# Sheet1.net
KiCad netlist of a schematic drawn in Altium Designer
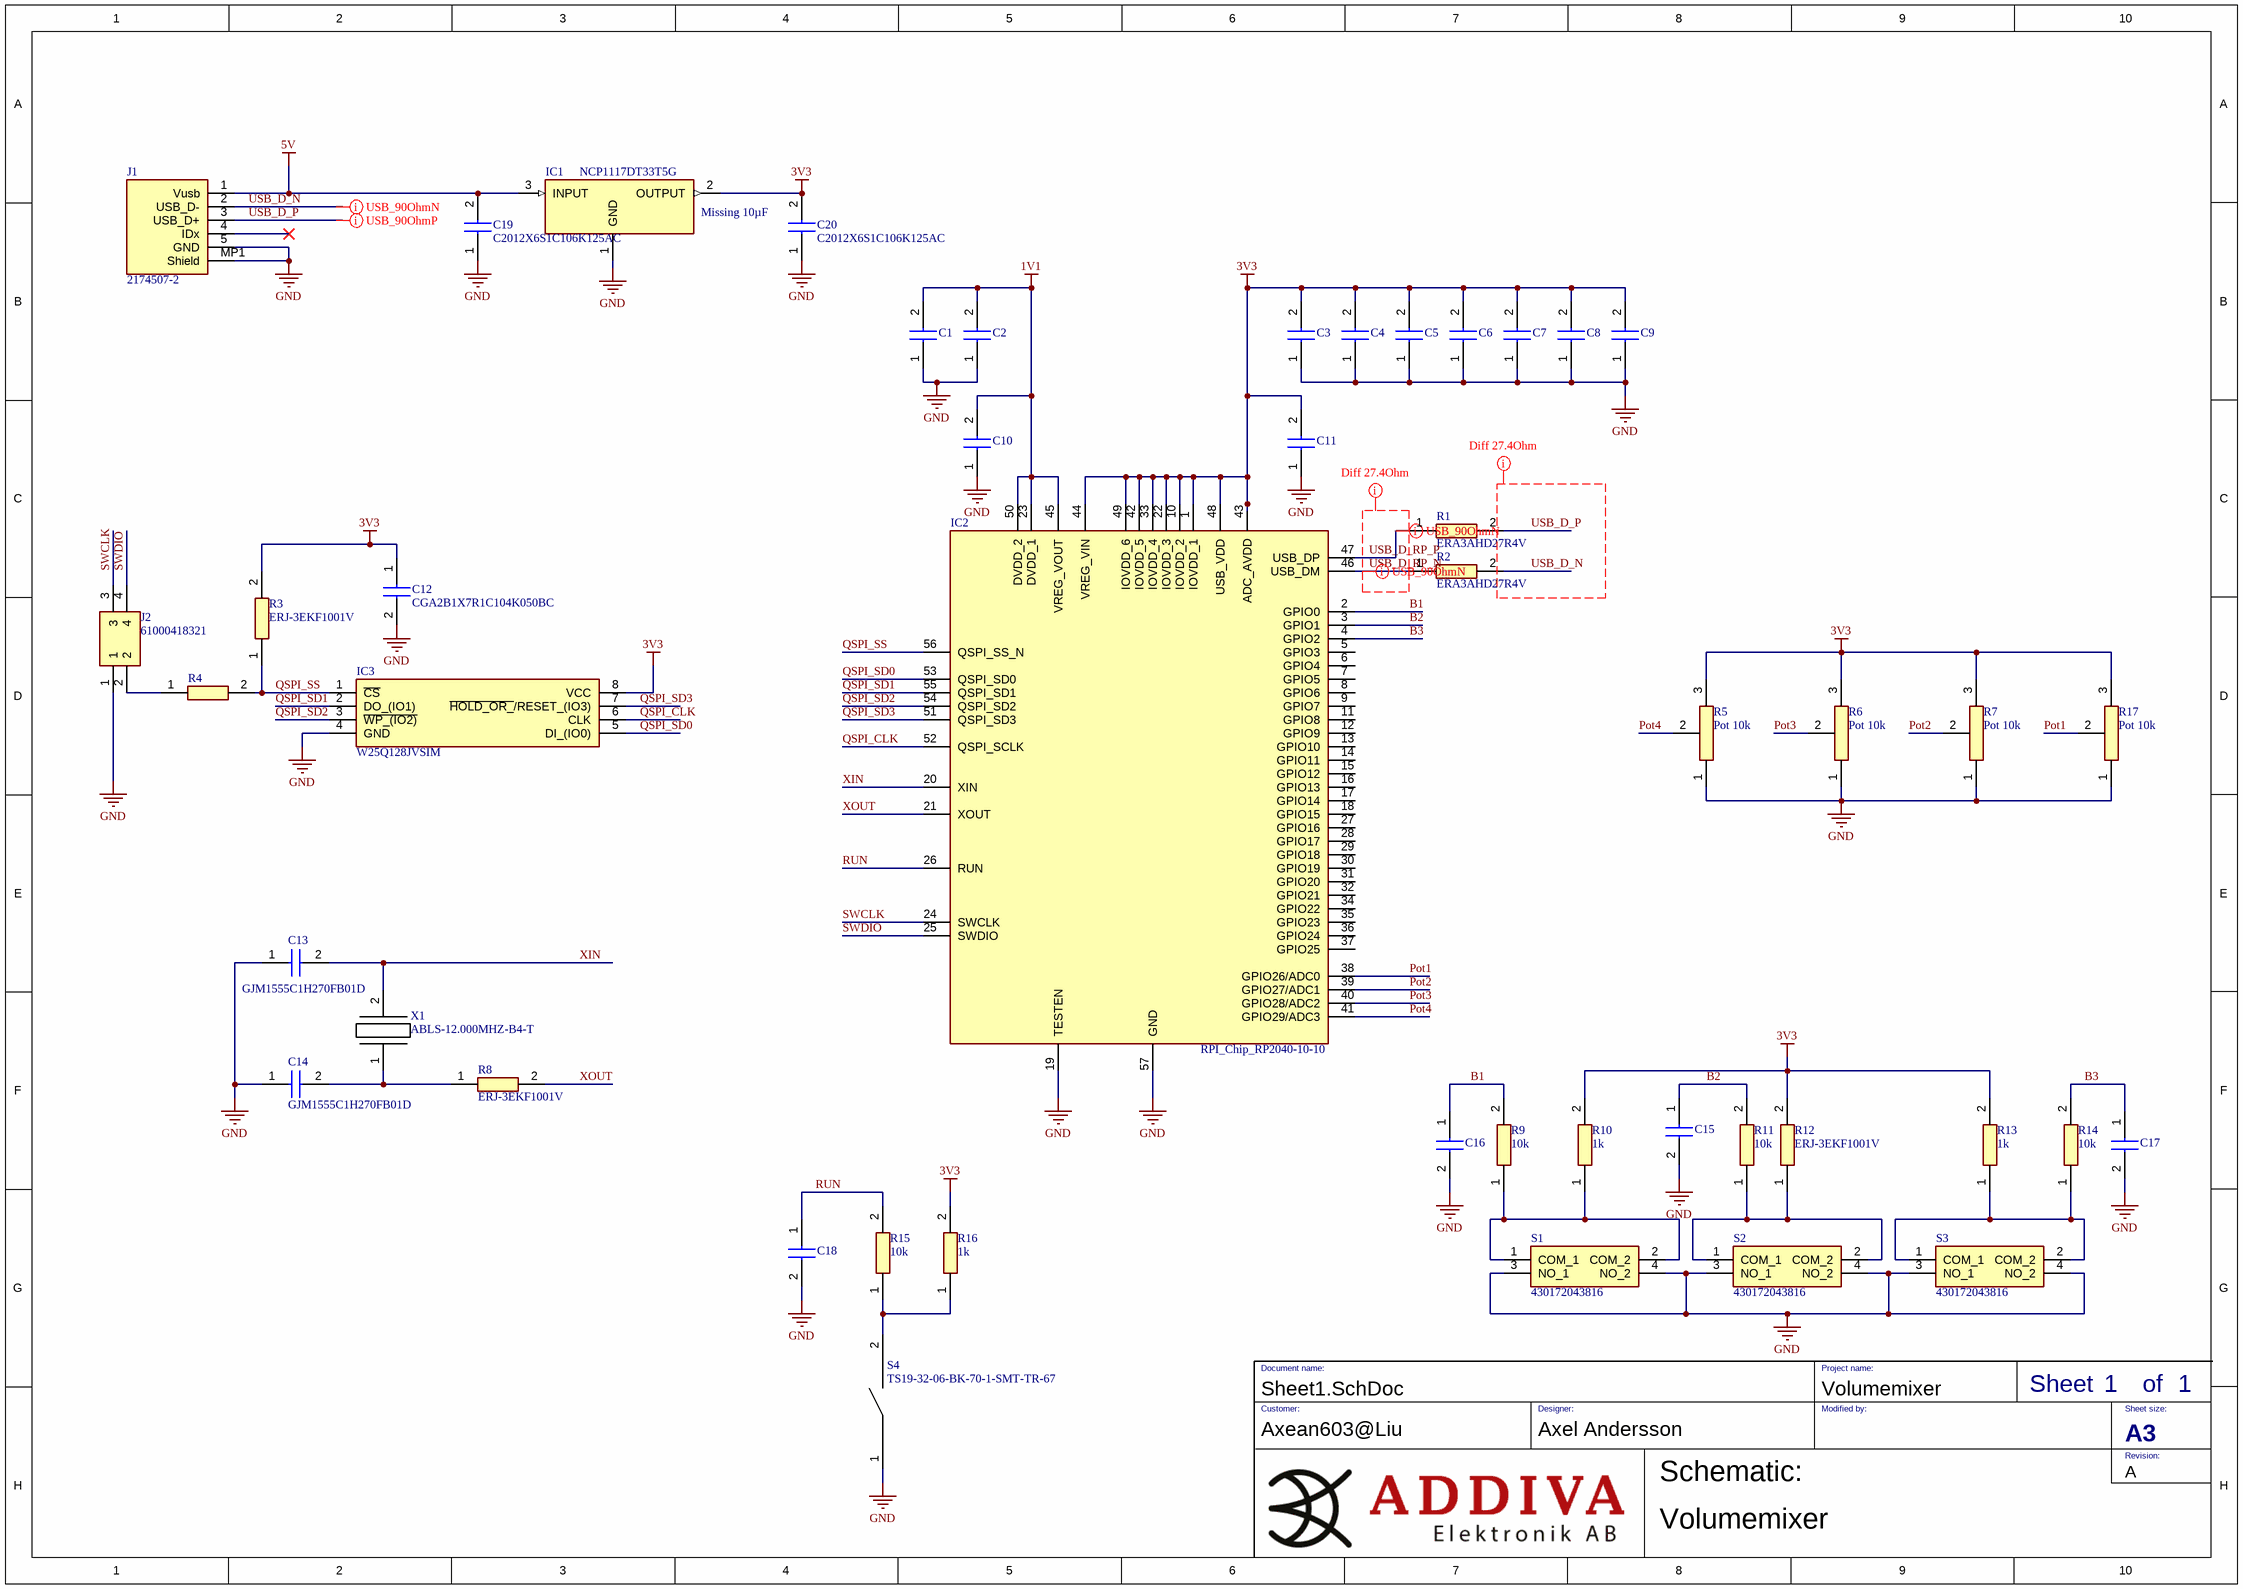
[diagram p0: Sheet1.SchDoc]

(export (version "E")
  (design (tool "Eeschema 10.0.6"))
  (components
    (comp (ref "C1")
      (value "CGA2B1X7R1C104K050BC")
      (footprint "PcbLib:CAPC1005X55N")
      (description "Capacitor 100nF 16V")
      (fields (field (name "MOUSER PART NUMBER") "810-CGA2B1X7R1C104K"))
      (libsource (lib "Schlib") (part "CGA2B1X7R1C104K050BC"))
    )
    (comp (ref "C2")
      (value "CGA2B1X7R1C104K050BC")
      (footprint "PcbLib:CAPC1005X55N")
      (description "Capacitor 100nF 16V")
      (fields (field (name "MOUSER PART NUMBER") "810-CGA2B1X7R1C104K"))
      (libsource (lib "Schlib") (part "CGA2B1X7R1C104K050BC"))
    )
    (comp (ref "C3")
      (value "CGA2B1X7R1C104K050BC")
      (footprint "PcbLib:CAPC1005X55N")
      (description "Capacitor 100nF 16V")
      (fields (field (name "MOUSER PART NUMBER") "810-CGA2B1X7R1C104K"))
      (libsource (lib "Schlib") (part "CGA2B1X7R1C104K050BC"))
    )
    (comp (ref "C4")
      (value "CGA2B1X7R1C104K050BC")
      (footprint "PcbLib:CAPC1005X55N")
      (description "Capacitor 100nF 16V")
      (fields (field (name "MOUSER PART NUMBER") "810-CGA2B1X7R1C104K"))
      (libsource (lib "Schlib") (part "CGA2B1X7R1C104K050BC"))
    )
    (comp (ref "C5")
      (value "CGA2B1X7R1C104K050BC")
      (footprint "PcbLib:CAPC1005X55N")
      (description "Capacitor 100nF 16V")
      (fields (field (name "MOUSER PART NUMBER") "810-CGA2B1X7R1C104K"))
      (libsource (lib "Schlib") (part "CGA2B1X7R1C104K050BC"))
    )
    (comp (ref "C6")
      (value "CGA2B1X7R1C104K050BC")
      (footprint "PcbLib:CAPC1005X55N")
      (description "Capacitor 100nF 16V")
      (fields (field (name "MOUSER PART NUMBER") "810-CGA2B1X7R1C104K"))
      (libsource (lib "Schlib") (part "CGA2B1X7R1C104K050BC"))
    )
    (comp (ref "C7")
      (value "CGA2B1X7R1C104K050BC")
      (footprint "PcbLib:CAPC1005X55N")
      (description "Capacitor 100nF 16V")
      (fields (field (name "MOUSER PART NUMBER") "810-CGA2B1X7R1C104K"))
      (libsource (lib "Schlib") (part "CGA2B1X7R1C104K050BC"))
    )
    (comp (ref "C8")
      (value "CGA2B1X7R1C104K050BC")
      (footprint "PcbLib:CAPC1005X55N")
      (description "Capacitor 100nF 16V")
      (fields (field (name "MOUSER PART NUMBER") "810-CGA2B1X7R1C104K"))
      (libsource (lib "Schlib") (part "CGA2B1X7R1C104K050BC"))
    )
    (comp (ref "C9")
      (value "CGA2B1X7R1C104K050BC")
      (footprint "PcbLib:CAPC1005X55N")
      (description "Capacitor 100nF 16V")
      (fields (field (name "MOUSER PART NUMBER") "810-CGA2B1X7R1C104K"))
      (libsource (lib "Schlib") (part "CGA2B1X7R1C104K050BC"))
    )
    (comp (ref "C10")
      (value "C1005X6S1C105K050BC")
      (footprint "PcbLib:C1005_Commercial")
      (description "Capacitor 0402 1µF 16V")
      (fields (field (name "MOUSER PART NUMBER") "810-C1005X6S1C105K"))
      (libsource (lib "Schlib") (part "C1005X6S1C105K050BC"))
    )
    (comp (ref "C11")
      (value "C1005X6S1C105K050BC")
      (footprint "PcbLib:C1005_Commercial")
      (description "Capacitor 0402 1µF 16V")
      (fields (field (name "MOUSER PART NUMBER") "810-C1005X6S1C105K"))
      (libsource (lib "Schlib") (part "C1005X6S1C105K050BC"))
    )
    (comp (ref "C12")
      (value "CGA2B1X7R1C104K050BC")
      (footprint "PcbLib:CAPC1005X55N")
      (description "Capacitor 100nF 16V")
      (fields (field (name "MOUSER PART NUMBER") "810-CGA2B1X7R1C104K"))
      (libsource (lib "Schlib") (part "CGA2B1X7R1C104K050BC"))
    )
    (comp (ref "C13")
      (value "GJM1555C1H270FB01D")
      (footprint "SamacSys:CAPC1005X55N")
      (description "Capacitor 27pF 50V")
      (fields (field (name "MOUSER PART NUMBER") "81-GJM1555C1H270FB1D"))
      (libsource (lib "Schlib") (part "GJM1555C1H270FB01D"))
    )
    (comp (ref "C14")
      (value "GJM1555C1H270FB01D")
      (footprint "SamacSys:CAPC1005X55N")
      (description "Capacitor 27pF 50V")
      (fields (field (name "MOUSER PART NUMBER") "81-GJM1555C1H270FB1D"))
      (libsource (lib "Schlib") (part "GJM1555C1H270FB01D"))
    )
    (comp (ref "C15")
      (value "C0402C105K9PAC")
      (footprint "PcbLib:CAPC1005X55N")
      (description "Capacitor 1µF 6V3 0402")
      (fields (field (name "MOUSER PART NUMBER") "80-C0402C105K9PAC"))
      (libsource (lib "Schlib") (part "C0402C105K9PAC"))
    )
    (comp (ref "C16")
      (value "C0402C105K9PAC")
      (footprint "PcbLib:CAPC1005X55N")
      (description "Capacitor 1µF 6V3 0402")
      (fields (field (name "MOUSER PART NUMBER") "80-C0402C105K9PAC"))
      (libsource (lib "Schlib") (part "C0402C105K9PAC"))
    )
    (comp (ref "C17")
      (value "C0402C105K9PAC")
      (footprint "PcbLib:CAPC1005X55N")
      (description "Capacitor 1µF 6V3 0402")
      (fields (field (name "MOUSER PART NUMBER") "80-C0402C105K9PAC"))
      (libsource (lib "Schlib") (part "C0402C105K9PAC"))
    )
    (comp (ref "C18")
      (value "C0402C105K9PAC")
      (footprint "PcbLib:CAPC1005X55N")
      (description "Capacitor 1µF 6V3 0402")
      (fields (field (name "MOUSER PART NUMBER") "80-C0402C105K9PAC"))
      (libsource (lib "Schlib") (part "C0402C105K9PAC"))
    )
    (comp (ref "C19")
      (value "C2012X6S1C106K125AC")
      (footprint "PcbLib:C2012_Commercial")
      (description "Capacitor 10µF 16V 0805")
      (fields (field (name "MOUSER PART NUMBER") "810-C2012X6S1C106K1C"))
      (libsource (lib "Schlib") (part "C2012X6S1C106K125AC"))
    )
    (comp (ref "C20")
      (value "C2012X6S1C106K125AC")
      (footprint "PcbLib:C2012_Commercial")
      (description "Capacitor 10µF 16V 0805")
      (fields (field (name "MOUSER PART NUMBER") "810-C2012X6S1C106K1C"))
      (libsource (lib "Schlib") (part "C2012X6S1C106K125AC"))
    )
    (comp (ref "IC1")
      (value "NCP1117DT33T5G")
      (footprint "PcbLib:TO229P990X238-4N")
      (description "LDO 3V3 out")
      (fields (field (name "MOUSER PART NUMBER") "863-NCP1117DT33T5G"))
      (libsource (lib "Schlib") (part "NCP1117DT33T5G"))
    )
    (comp (ref "IC2")
      (value "RPI_Chip_RP2040-10-10")
      (footprint "PcbLib:QFN40P700X700X90-57N-D")
      (description "RP2040 MCU")
      (fields
        (field (name "MANUFACTURER_PART_NUMBER") "RPI Chip RP2040-10-10")
        (field (name "MOUSER PART NUMBER") "358-RP2040CHIP-10-10")
      )
      (libsource (lib "Schlib") (part "RPI_Chip_RP2040-10-10"))
    )
    (comp (ref "IC3")
      (value "W25Q128JVSIM")
      (footprint "SamacSys:SOIC127P790X216-8N")
      (description "128 SPI Nor flash")
      (fields (field (name "MOUSER PART NUMBER") "454-W25Q128JVSIM"))
      (libsource (lib "Schlib") (part "W25Q128JVSIM"))
    )
    (comp (ref "J1")
      (value "2174507-2")
      (footprint "SamacSys:21745072")
      (description "Micro USB Connector")
      (fields (field (name "MOUSER PART NUMBER") "571-2174507-2"))
      (libsource (lib "Schlib") (part "2174507-2"))
    )
    (comp (ref "J2")
      (value "61000418321")
      (footprint "PcbLib:HUSRSP4W64P254_1016X254X854P")
      (description "Connector")
      (libsource (lib "Schlib") (part "61000418321"))
    )
    (comp (ref "R1")
      (value "ERA3AHD27R4V")
      (footprint "PcbLib:ERA3A_(0603)")
      (description "Resistor 0603 27.4Ohm")
      (libsource (lib "Schlib") (part "ERA3AHD27R4V"))
    )
    (comp (ref "R2")
      (value "ERA3AHD27R4V")
      (footprint "PcbLib:ERA3A_(0603)")
      (description "Resistor 0603 27.4Ohm")
      (libsource (lib "Schlib") (part "ERA3AHD27R4V"))
    )
    (comp (ref "R3")
      (value "ERJ-3EKF1001V")
      (footprint "PcbLib:ERJ3EK_(0603)")
      (description "Resistor 1k 0603")
      (fields (field (name "MOUSER PART NUMBER") "667-ERJ-3EKF1001V"))
      (libsource (lib "Schlib") (part "ERJ-3EKF1001V"))
    )
    (comp (ref "R4")
      (value "ERJ-3EKF1001V")
      (footprint "PcbLib:ERJ3EK_(0603)")
      (description "Resistor 1k 0603")
      (fields (field (name "MOUSER PART NUMBER") "667-ERJ-3EKF1001V"))
      (libsource (lib "") (part "ERJ-3EKF1001V_1"))
    )
    (comp (ref "R5")
      (value "Pot 10k")
      (footprint "PcbLib:P0915NFC15BR10K")
      (description "POT 10k")
      (fields
        (field (name "MANUFACTURER_PART_NUMBER") "P0915N-FC15BR10K")
        (field (name "MOUSER PART NUMBER") "858-P0915N-FC15BR10K")
      )
      (libsource (lib "Schlib") (part "P0915N-FC15BR10K"))
    )
    (comp (ref "R6")
      (value "Pot 10k")
      (footprint "PcbLib:P0915NFC15BR10K")
      (description "POT 10k")
      (fields
        (field (name "MANUFACTURER_PART_NUMBER") "P0915N-FC15BR10K")
        (field (name "MOUSER PART NUMBER") "858-P0915N-FC15BR10K")
      )
      (libsource (lib "Schlib") (part "P0915N-FC15BR10K"))
    )
    (comp (ref "R7")
      (value "Pot 10k")
      (footprint "PcbLib:P0915NFC15BR10K")
      (description "POT 10k")
      (fields
        (field (name "MANUFACTURER_PART_NUMBER") "P0915N-FC15BR10K")
        (field (name "MOUSER PART NUMBER") "858-P0915N-FC15BR10K")
      )
      (libsource (lib "Schlib") (part "P0915N-FC15BR10K"))
    )
    (comp (ref "R8")
      (value "ERJ-3EKF1001V")
      (footprint "SamacSys:ERJ3EK_(0603)")
      (description "Resistor 1k 0603")
      (fields (field (name "MOUSER PART NUMBER") "667-ERJ-3EKF1001V"))
      (libsource (lib "") (part "ERJ-3EKF1001V_1"))
    )
    (comp (ref "R9")
      (value "10k")
      (footprint "PcbLib:ERJ3EK_(0603)")
      (description "Resistor 10k 0603")
      (fields
        (field (name "MANUFACTURER_PART_NUMBER") "ERJ-3EKF1001V")
        (field (name "MOUSER PART NUMBER") "667-ERJ-3EKF1001V")
      )
      (libsource (lib "Schlib") (part "ERJ-3EKF1001V"))
    )
    (comp (ref "R10")
      (value "1k")
      (footprint "PcbLib:ERJ3EK_(0603)")
      (description "Resistor 1k 0603")
      (fields
        (field (name "MANUFACTURER_PART_NUMBER") "ERJ-3EKF1001V")
        (field (name "MOUSER PART NUMBER") "667-ERJ-3EKF1001V")
      )
      (libsource (lib "Schlib") (part "ERJ-3EKF1001V"))
    )
    (comp (ref "R11")
      (value "10k")
      (footprint "PcbLib:ERJ3EK_(0603)")
      (description "Resistor 10k 0603")
      (fields
        (field (name "MANUFACTURER_PART_NUMBER") "ERJ-3EKF1001V")
        (field (name "MOUSER PART NUMBER") "667-ERJ-3EKF1001V")
      )
      (libsource (lib "Schlib") (part "ERJ-3EKF1001V"))
    )
    (comp (ref "R12")
      (value "ERJ-3EKF1001V")
      (footprint "PcbLib:ERJ3EK_(0603)")
      (description "Resistor 1k 0603")
      (fields (field (name "MOUSER PART NUMBER") "667-ERJ-3EKF1001V"))
      (libsource (lib "Schlib") (part "ERJ-3EKF1001V"))
    )
    (comp (ref "R13")
      (value "1k")
      (footprint "PcbLib:ERJ3EK_(0603)")
      (description "Resistor 1k 0603")
      (fields
        (field (name "MANUFACTURER_PART_NUMBER") "ERJ-3EKF1001V")
        (field (name "MOUSER PART NUMBER") "667-ERJ-3EKF1001V")
      )
      (libsource (lib "Schlib") (part "ERJ-3EKF1001V"))
    )
    (comp (ref "R14")
      (value "10k")
      (footprint "PcbLib:ERJ3EK_(0603)")
      (description "Resistor 10k 0603")
      (fields
        (field (name "MANUFACTURER_PART_NUMBER") "ERJ-3EKF1001V")
        (field (name "MOUSER PART NUMBER") "667-ERJ-3EKF1001V")
      )
      (libsource (lib "Schlib") (part "ERJ-3EKF1001V"))
    )
    (comp (ref "R15")
      (value "10k")
      (footprint "PcbLib:ERJ3EK_(0603)")
      (description "Resistor 10k 0603")
      (fields
        (field (name "MANUFACTURER_PART_NUMBER") "ERJ-3EKF1001V")
        (field (name "MOUSER PART NUMBER") "667-ERJ-3EKF1001V")
      )
      (libsource (lib "Schlib") (part "ERJ-3EKF1001V"))
    )
    (comp (ref "R16")
      (value "1k")
      (footprint "PcbLib:ERJ3EK_(0603)")
      (description "Resistor 1k 0603")
      (fields
        (field (name "MANUFACTURER_PART_NUMBER") "ERJ-3EKF1001V")
        (field (name "MOUSER PART NUMBER") "667-ERJ-3EKF1001V")
      )
      (libsource (lib "Schlib") (part "ERJ-3EKF1001V"))
    )
    (comp (ref "R17")
      (value "Pot 10k")
      (footprint "PcbLib:P0915NFC15BR10K")
      (description "POT 10k")
      (fields
        (field (name "MANUFACTURER_PART_NUMBER") "P0915N-FC15BR10K")
        (field (name "MOUSER PART NUMBER") "858-P0915N-FC15BR10K")
      )
      (libsource (lib "Schlib") (part "P0915N-FC15BR10K"))
    )
    (comp (ref "S1")
      (value "430172043816")
      (footprint "PcbLib:430172043816")
      (description "Switch")
      (fields (field (name "MOUSER PART NUMBER") "710-430172043816"))
      (libsource (lib "Schlib") (part "430172043816"))
    )
    (comp (ref "S2")
      (value "430172043816")
      (footprint "PcbLib:430172043816")
      (description "Switch")
      (fields (field (name "MOUSER PART NUMBER") "710-430172043816"))
      (libsource (lib "Schlib") (part "430172043816"))
    )
    (comp (ref "S3")
      (value "430172043816")
      (footprint "PcbLib:430172043816")
      (description "Switch")
      (fields (field (name "MOUSER PART NUMBER") "710-430172043816"))
      (libsource (lib "Schlib") (part "430172043816"))
    )
    (comp (ref "S4")
      (value "TS19-32-06-BK-70-1-SMT-TR-67")
      (footprint "PcbLib:TS193206BK701SMTTR67")
      (description "Switch")
      (fields (field (name "MOUSER PART NUMBER") "179-TS193206BK701SM"))
      (libsource (lib "Schlib") (part "TS19-32-06-BK-70-1-SMT-TR-67"))
    )
    (comp (ref "X1")
      (value "ABLS-12.000MHZ-B4-T")
      (footprint "PcbLib:HC/49US-(AT49)_1")
      (description "Crystal oscillator")
      (fields (field (name "MOUSER PART NUMBER") "815-ABLS-12.0M-T"))
      (libsource (lib "Schlib") (part "ABLS-12.000MHZ-B4-T"))
    )
  )
  (nets
    (net (code "1") (name "/B1") (class "Default")
      (node (ref "C16") (pin "1") (pinfunction "1_1") (pintype "passive"))
      (node (ref "IC2") (pin "2") (pinfunction "GPIO0_2") (pintype "passive"))
      (node (ref "R9") (pin "2") (pinfunction "2_2") (pintype "passive"))
    )
    (net (code "2") (name "/B2") (class "Default")
      (node (ref "C15") (pin "1") (pinfunction "1_1") (pintype "passive"))
      (node (ref "IC2") (pin "3") (pinfunction "GPIO1_3") (pintype "passive"))
      (node (ref "R11") (pin "2") (pinfunction "2_2") (pintype "passive"))
    )
    (net (code "3") (name "/B3") (class "Default")
      (node (ref "C17") (pin "1") (pinfunction "1_1") (pintype "passive"))
      (node (ref "IC2") (pin "4") (pinfunction "GPIO2_4") (pintype "passive"))
      (node (ref "R14") (pin "2") (pinfunction "2_2") (pintype "passive"))
    )
    (net (code "4") (name "/Pot1") (class "Default")
      (node (ref "IC2") (pin "38") (pinfunction "GPIO26/ADC0_38") (pintype "passive"))
      (node (ref "R17") (pin "2") (pinfunction "2_2") (pintype "passive"))
    )
    (net (code "5") (name "/Pot2") (class "Default")
      (node (ref "IC2") (pin "39") (pinfunction "GPIO27/ADC1_39") (pintype "passive"))
      (node (ref "R7") (pin "2") (pinfunction "2_2") (pintype "passive"))
    )
    (net (code "6") (name "/Pot3") (class "Default")
      (node (ref "IC2") (pin "40") (pinfunction "GPIO28/ADC2_40") (pintype "passive"))
      (node (ref "R6") (pin "2") (pinfunction "2_2") (pintype "passive"))
    )
    (net (code "7") (name "/Pot4") (class "Default")
      (node (ref "IC2") (pin "41") (pinfunction "GPIO29/ADC3_41") (pintype "passive"))
      (node (ref "R5") (pin "2") (pinfunction "2_2") (pintype "passive"))
    )
    (net (code "8") (name "/QSPI_CLK") (class "Default")
      (node (ref "IC2") (pin "52") (pinfunction "QSPI_SCLK_52") (pintype "passive"))
      (node (ref "IC3") (pin "6") (pinfunction "CLK_6") (pintype "passive"))
    )
    (net (code "9") (name "/QSPI_SD0") (class "Default")
      (node (ref "IC2") (pin "53") (pinfunction "QSPI_SD0_53") (pintype "passive"))
      (node (ref "IC3") (pin "5") (pinfunction "DI_(IO0)_5") (pintype "passive"))
    )
    (net (code "10") (name "/QSPI_SD1") (class "Default")
      (node (ref "IC2") (pin "55") (pinfunction "QSPI_SD1_55") (pintype "passive"))
      (node (ref "IC3") (pin "2") (pinfunction "DO_(IO1)_2") (pintype "passive"))
    )
    (net (code "11") (name "/QSPI_SD2") (class "Default")
      (node (ref "IC2") (pin "54") (pinfunction "QSPI_SD2_54") (pintype "passive"))
      (node (ref "IC3") (pin "3") (pinfunction "~{WP_(IO2)}_3") (pintype "passive"))
    )
    (net (code "12") (name "/QSPI_SD3") (class "Default")
      (node (ref "IC2") (pin "51") (pinfunction "QSPI_SD3_51") (pintype "passive"))
      (node (ref "IC3") (pin "7") (pinfunction "~{HOLD_OR_}/RESET_(IO3)_7") (pintype "passive"))
    )
    (net (code "13") (name "/QSPI_SS") (class "Default")
      (node (ref "IC2") (pin "56") (pinfunction "QSPI_SS_N_56") (pintype "passive"))
      (node (ref "IC3") (pin "1") (pinfunction "~{CS}_1") (pintype "passive"))
      (node (ref "R3") (pin "1") (pinfunction "1_1") (pintype "passive"))
      (node (ref "R4") (pin "2") (pinfunction "2_2") (pintype "passive"))
    )
    (net (code "14") (name "/RUN") (class "Default")
      (node (ref "C18") (pin "1") (pinfunction "1_1") (pintype "passive"))
      (node (ref "IC2") (pin "26") (pinfunction "RUN_26") (pintype "passive"))
      (node (ref "R15") (pin "2") (pinfunction "2_2") (pintype "passive"))
    )
    (net (code "15") (name "/SWCLK") (class "Default")
      (node (ref "IC2") (pin "24") (pinfunction "SWCLK_24") (pintype "passive"))
      (node (ref "J2") (pin "3") (pinfunction "3_3") (pintype "passive"))
    )
    (net (code "16") (name "/SWDIO") (class "Default")
      (node (ref "IC2") (pin "25") (pinfunction "SWDIO_25") (pintype "passive"))
      (node (ref "J2") (pin "4") (pinfunction "4_4") (pintype "passive"))
    )
    (net (code "17") (name "/USB_D_N") (class "Default")
      (node (ref "J1") (pin "2") (pinfunction "USB_D-_2") (pintype "passive"))
      (node (ref "R2") (pin "2") (pinfunction "2_2") (pintype "passive"))
    )
    (net (code "18") (name "/USB_D_P") (class "Default")
      (node (ref "J1") (pin "3") (pinfunction "USB_D+_3") (pintype "passive"))
      (node (ref "R1") (pin "2") (pinfunction "2_2") (pintype "passive"))
    )
    (net (code "19") (name "/USB_D_RP_N") (class "Default")
      (node (ref "IC2") (pin "46") (pinfunction "USB_DM_46") (pintype "passive"))
      (node (ref "R2") (pin "1") (pinfunction "1_1") (pintype "passive"))
    )
    (net (code "20") (name "/USB_D_RP_P") (class "Default")
      (node (ref "IC2") (pin "47") (pinfunction "USB_DP_47") (pintype "passive"))
      (node (ref "R1") (pin "1") (pinfunction "1_1") (pintype "passive"))
    )
    (net (code "21") (name "/XIN") (class "Default")
      (node (ref "C13") (pin "2") (pinfunction "2_2") (pintype "passive"))
      (node (ref "IC2") (pin "20") (pinfunction "XIN_20") (pintype "passive"))
      (node (ref "X1") (pin "2") (pinfunction "2_2") (pintype "passive"))
    )
    (net (code "22") (name "/XOUT") (class "Default")
      (node (ref "IC2") (pin "21") (pinfunction "XOUT_21") (pintype "passive"))
      (node (ref "R8") (pin "2") (pinfunction "2_2") (pintype "passive"))
    )
    (net (code "23") (name "1V1") (class "Default")
      (node (ref "C1") (pin "2") (pinfunction "2_2") (pintype "passive"))
      (node (ref "C10") (pin "2") (pinfunction "2_2") (pintype "passive"))
      (node (ref "C2") (pin "2") (pinfunction "2_2") (pintype "passive"))
      (node (ref "IC2") (pin "23") (pinfunction "DVDD_1_23") (pintype "passive"))
      (node (ref "IC2") (pin "45") (pinfunction "VREG_VOUT_45") (pintype "passive"))
      (node (ref "IC2") (pin "50") (pinfunction "DVDD_2_50") (pintype "passive"))
    )
    (net (code "24") (name "3V3") (class "Default")
      (node (ref "C11") (pin "2") (pinfunction "2_2") (pintype "passive"))
      (node (ref "C12") (pin "1") (pinfunction "1_1") (pintype "passive"))
      (node (ref "C20") (pin "2") (pinfunction "2_2") (pintype "passive"))
      (node (ref "C3") (pin "2") (pinfunction "2_2") (pintype "passive"))
      (node (ref "C4") (pin "2") (pinfunction "2_2") (pintype "passive"))
      (node (ref "C5") (pin "2") (pinfunction "2_2") (pintype "passive"))
      (node (ref "C6") (pin "2") (pinfunction "2_2") (pintype "passive"))
      (node (ref "C7") (pin "2") (pinfunction "2_2") (pintype "passive"))
      (node (ref "C8") (pin "2") (pinfunction "2_2") (pintype "passive"))
      (node (ref "C9") (pin "2") (pinfunction "2_2") (pintype "passive"))
      (node (ref "IC1") (pin "2") (pinfunction "OUTPUT_2") (pintype "output"))
      (node (ref "IC2") (pin "1") (pinfunction "IOVDD_1_1") (pintype "passive"))
      (node (ref "IC2") (pin "10") (pinfunction "IOVDD_2_10") (pintype "passive"))
      (node (ref "IC2") (pin "22") (pinfunction "IOVDD_3_22") (pintype "passive"))
      (node (ref "IC2") (pin "33") (pinfunction "IOVDD_4_33") (pintype "passive"))
      (node (ref "IC2") (pin "42") (pinfunction "IOVDD_5_42") (pintype "passive"))
      (node (ref "IC2") (pin "43") (pinfunction "ADC_AVDD_43") (pintype "passive"))
      (node (ref "IC2") (pin "44") (pinfunction "VREG_VIN_44") (pintype "passive"))
      (node (ref "IC2") (pin "48") (pinfunction "USB_VDD_48") (pintype "passive"))
      (node (ref "IC2") (pin "49") (pinfunction "IOVDD_6_49") (pintype "passive"))
      (node (ref "IC3") (pin "8") (pinfunction "VCC_8") (pintype "passive"))
      (node (ref "R10") (pin "2") (pinfunction "2_2") (pintype "passive"))
      (node (ref "R12") (pin "2") (pinfunction "2_2") (pintype "passive"))
      (node (ref "R13") (pin "2") (pinfunction "2_2") (pintype "passive"))
      (node (ref "R16") (pin "2") (pinfunction "2_2") (pintype "passive"))
      (node (ref "R17") (pin "3") (pinfunction "3_3") (pintype "passive"))
      (node (ref "R3") (pin "2") (pinfunction "2_2") (pintype "passive"))
      (node (ref "R5") (pin "3") (pinfunction "3_3") (pintype "passive"))
      (node (ref "R6") (pin "3") (pinfunction "3_3") (pintype "passive"))
      (node (ref "R7") (pin "3") (pinfunction "3_3") (pintype "passive"))
    )
    (net (code "25") (name "5V") (class "Default")
      (node (ref "C19") (pin "2") (pinfunction "2_2") (pintype "passive"))
      (node (ref "IC1") (pin "3") (pinfunction "INPUT_3") (pintype "input"))
      (node (ref "J1") (pin "1") (pinfunction "Vusb_1") (pintype "passive"))
    )
    (net (code "26") (name "GND") (class "Default")
      (node (ref "C1") (pin "1") (pinfunction "1_1") (pintype "passive"))
      (node (ref "C10") (pin "1") (pinfunction "1_1") (pintype "passive"))
      (node (ref "C11") (pin "1") (pinfunction "1_1") (pintype "passive"))
      (node (ref "C12") (pin "2") (pinfunction "2_2") (pintype "passive"))
      (node (ref "C13") (pin "1") (pinfunction "1_1") (pintype "passive"))
      (node (ref "C14") (pin "1") (pinfunction "1_1") (pintype "passive"))
      (node (ref "C15") (pin "2") (pinfunction "2_2") (pintype "passive"))
      (node (ref "C16") (pin "2") (pinfunction "2_2") (pintype "passive"))
      (node (ref "C17") (pin "2") (pinfunction "2_2") (pintype "passive"))
      (node (ref "C18") (pin "2") (pinfunction "2_2") (pintype "passive"))
      (node (ref "C19") (pin "1") (pinfunction "1_1") (pintype "passive"))
      (node (ref "C2") (pin "1") (pinfunction "1_1") (pintype "passive"))
      (node (ref "C20") (pin "1") (pinfunction "1_1") (pintype "passive"))
      (node (ref "C3") (pin "1") (pinfunction "1_1") (pintype "passive"))
      (node (ref "C4") (pin "1") (pinfunction "1_1") (pintype "passive"))
      (node (ref "C5") (pin "1") (pinfunction "1_1") (pintype "passive"))
      (node (ref "C6") (pin "1") (pinfunction "1_1") (pintype "passive"))
      (node (ref "C7") (pin "1") (pinfunction "1_1") (pintype "passive"))
      (node (ref "C8") (pin "1") (pinfunction "1_1") (pintype "passive"))
      (node (ref "C9") (pin "1") (pinfunction "1_1") (pintype "passive"))
      (node (ref "IC1") (pin "1") (pinfunction "GND_1") (pintype "power_in"))
      (node (ref "IC2") (pin "19") (pinfunction "TESTEN_19") (pintype "passive"))
      (node (ref "IC2") (pin "57") (pinfunction "GND_57") (pintype "passive"))
      (node (ref "IC3") (pin "4") (pinfunction "GND_4") (pintype "passive"))
      (node (ref "J1") (pin "5") (pinfunction "GND_5") (pintype "passive"))
      (node (ref "J1") (pin "MP1") (pinfunction "Shield_MP1") (pintype "passive"))
      (node (ref "J2") (pin "1") (pinfunction "1_1") (pintype "passive"))
      (node (ref "R17") (pin "1") (pinfunction "1_1") (pintype "passive"))
      (node (ref "R5") (pin "1") (pinfunction "1_1") (pintype "passive"))
      (node (ref "R6") (pin "1") (pinfunction "1_1") (pintype "passive"))
      (node (ref "R7") (pin "1") (pinfunction "1_1") (pintype "passive"))
      (node (ref "S1") (pin "3") (pinfunction "NO_1_3") (pintype "passive"))
      (node (ref "S1") (pin "4") (pinfunction "NO_2_4") (pintype "passive"))
      (node (ref "S2") (pin "3") (pinfunction "NO_1_3") (pintype "passive"))
      (node (ref "S2") (pin "4") (pinfunction "NO_2_4") (pintype "passive"))
      (node (ref "S3") (pin "3") (pinfunction "NO_1_3") (pintype "passive"))
      (node (ref "S3") (pin "4") (pinfunction "NO_2_4") (pintype "passive"))
      (node (ref "S4") (pin "1") (pinfunction "1_1") (pintype "passive"))
    )
    (net (code "27") (name "Net-(C14-Pad2)") (class "Default")
      (node (ref "C14") (pin "2") (pinfunction "2_2") (pintype "passive"))
      (node (ref "R8") (pin "1") (pinfunction "1_1") (pintype "passive"))
      (node (ref "X1") (pin "1") (pinfunction "1_1") (pintype "passive"))
    )
    (net (code "28") (name "Net-(J2-Pad2)") (class "Default")
      (node (ref "J2") (pin "2") (pinfunction "2_2") (pintype "passive"))
      (node (ref "R4") (pin "1") (pinfunction "1_1") (pintype "passive"))
    )
    (net (code "29") (name "Net-(R15-Pad1)") (class "Default")
      (node (ref "R15") (pin "1") (pinfunction "1_1") (pintype "passive"))
      (node (ref "R16") (pin "1") (pinfunction "1_1") (pintype "passive"))
      (node (ref "S4") (pin "2") (pinfunction "2_2") (pintype "passive"))
    )
    (net (code "30") (name "Net-(S1-COM_1)") (class "Default")
      (node (ref "R10") (pin "1") (pinfunction "1_1") (pintype "passive"))
      (node (ref "R9") (pin "1") (pinfunction "1_1") (pintype "passive"))
      (node (ref "S1") (pin "1") (pinfunction "COM_1_1") (pintype "passive"))
      (node (ref "S1") (pin "2") (pinfunction "COM_2_2") (pintype "passive"))
    )
    (net (code "31") (name "Net-(S2-COM_1)") (class "Default")
      (node (ref "R11") (pin "1") (pinfunction "1_1") (pintype "passive"))
      (node (ref "R12") (pin "1") (pinfunction "1_1") (pintype "passive"))
      (node (ref "S2") (pin "1") (pinfunction "COM_1_1") (pintype "passive"))
      (node (ref "S2") (pin "2") (pinfunction "COM_2_2") (pintype "passive"))
    )
    (net (code "32") (name "Net-(S3-COM_1)") (class "Default")
      (node (ref "R13") (pin "1") (pinfunction "1_1") (pintype "passive"))
      (node (ref "R14") (pin "1") (pinfunction "1_1") (pintype "passive"))
      (node (ref "S3") (pin "1") (pinfunction "COM_1_1") (pintype "passive"))
      (node (ref "S3") (pin "2") (pinfunction "COM_2_2") (pintype "passive"))
    )
    (net (code "33") (name "unconnected-(IC2-GPIO3-Pad5)") (class "Default")
      (node (ref "IC2") (pin "5") (pinfunction "GPIO3_5") (pintype "passive"))
    )
    (net (code "34") (name "unconnected-(IC2-GPIO4-Pad6)") (class "Default")
      (node (ref "IC2") (pin "6") (pinfunction "GPIO4_6") (pintype "passive"))
    )
    (net (code "35") (name "unconnected-(IC2-GPIO5-Pad7)") (class "Default")
      (node (ref "IC2") (pin "7") (pinfunction "GPIO5_7") (pintype "passive"))
    )
    (net (code "36") (name "unconnected-(IC2-GPIO6-Pad8)") (class "Default")
      (node (ref "IC2") (pin "8") (pinfunction "GPIO6_8") (pintype "passive"))
    )
    (net (code "37") (name "unconnected-(IC2-GPIO7-Pad9)") (class "Default")
      (node (ref "IC2") (pin "9") (pinfunction "GPIO7_9") (pintype "passive"))
    )
    (net (code "38") (name "unconnected-(IC2-GPIO8-Pad11)") (class "Default")
      (node (ref "IC2") (pin "11") (pinfunction "GPIO8_11") (pintype "passive"))
    )
    (net (code "39") (name "unconnected-(IC2-GPIO9-Pad12)") (class "Default")
      (node (ref "IC2") (pin "12") (pinfunction "GPIO9_12") (pintype "passive"))
    )
    (net (code "40") (name "unconnected-(IC2-GPIO10-Pad13)") (class "Default")
      (node (ref "IC2") (pin "13") (pinfunction "GPIO10_13") (pintype "passive"))
    )
    (net (code "41") (name "unconnected-(IC2-GPIO11-Pad14)") (class "Default")
      (node (ref "IC2") (pin "14") (pinfunction "GPIO11_14") (pintype "passive"))
    )
    (net (code "42") (name "unconnected-(IC2-GPIO12-Pad15)") (class "Default")
      (node (ref "IC2") (pin "15") (pinfunction "GPIO12_15") (pintype "passive"))
    )
    (net (code "43") (name "unconnected-(IC2-GPIO13-Pad16)") (class "Default")
      (node (ref "IC2") (pin "16") (pinfunction "GPIO13_16") (pintype "passive"))
    )
    (net (code "44") (name "unconnected-(IC2-GPIO14-Pad17)") (class "Default")
      (node (ref "IC2") (pin "17") (pinfunction "GPIO14_17") (pintype "passive"))
    )
    (net (code "45") (name "unconnected-(IC2-GPIO15-Pad18)") (class "Default")
      (node (ref "IC2") (pin "18") (pinfunction "GPIO15_18") (pintype "passive"))
    )
    (net (code "46") (name "unconnected-(IC2-GPIO16-Pad27)") (class "Default")
      (node (ref "IC2") (pin "27") (pinfunction "GPIO16_27") (pintype "passive"))
    )
    (net (code "47") (name "unconnected-(IC2-GPIO17-Pad28)") (class "Default")
      (node (ref "IC2") (pin "28") (pinfunction "GPIO17_28") (pintype "passive"))
    )
    (net (code "48") (name "unconnected-(IC2-GPIO18-Pad29)") (class "Default")
      (node (ref "IC2") (pin "29") (pinfunction "GPIO18_29") (pintype "passive"))
    )
    (net (code "49") (name "unconnected-(IC2-GPIO19-Pad30)") (class "Default")
      (node (ref "IC2") (pin "30") (pinfunction "GPIO19_30") (pintype "passive"))
    )
    (net (code "50") (name "unconnected-(IC2-GPIO20-Pad31)") (class "Default")
      (node (ref "IC2") (pin "31") (pinfunction "GPIO20_31") (pintype "passive"))
    )
    (net (code "51") (name "unconnected-(IC2-GPIO21-Pad32)") (class "Default")
      (node (ref "IC2") (pin "32") (pinfunction "GPIO21_32") (pintype "passive"))
    )
    (net (code "52") (name "unconnected-(IC2-GPIO22-Pad34)") (class "Default")
      (node (ref "IC2") (pin "34") (pinfunction "GPIO22_34") (pintype "passive"))
    )
    (net (code "53") (name "unconnected-(IC2-GPIO23-Pad35)") (class "Default")
      (node (ref "IC2") (pin "35") (pinfunction "GPIO23_35") (pintype "passive"))
    )
    (net (code "54") (name "unconnected-(IC2-GPIO24-Pad36)") (class "Default")
      (node (ref "IC2") (pin "36") (pinfunction "GPIO24_36") (pintype "passive"))
    )
    (net (code "55") (name "unconnected-(IC2-GPIO25-Pad37)") (class "Default")
      (node (ref "IC2") (pin "37") (pinfunction "GPIO25_37") (pintype "passive"))
    )
    (net (code "56") (name "unconnected-(J1-IDx-Pad4)") (class "Default")
      (node (ref "J1") (pin "4") (pinfunction "IDx_4") (pintype "passive+no_connect"))
    )
  )
)
